# 524656_003__3.net
KiCad netlist of a schematic drawn in Altium Designer
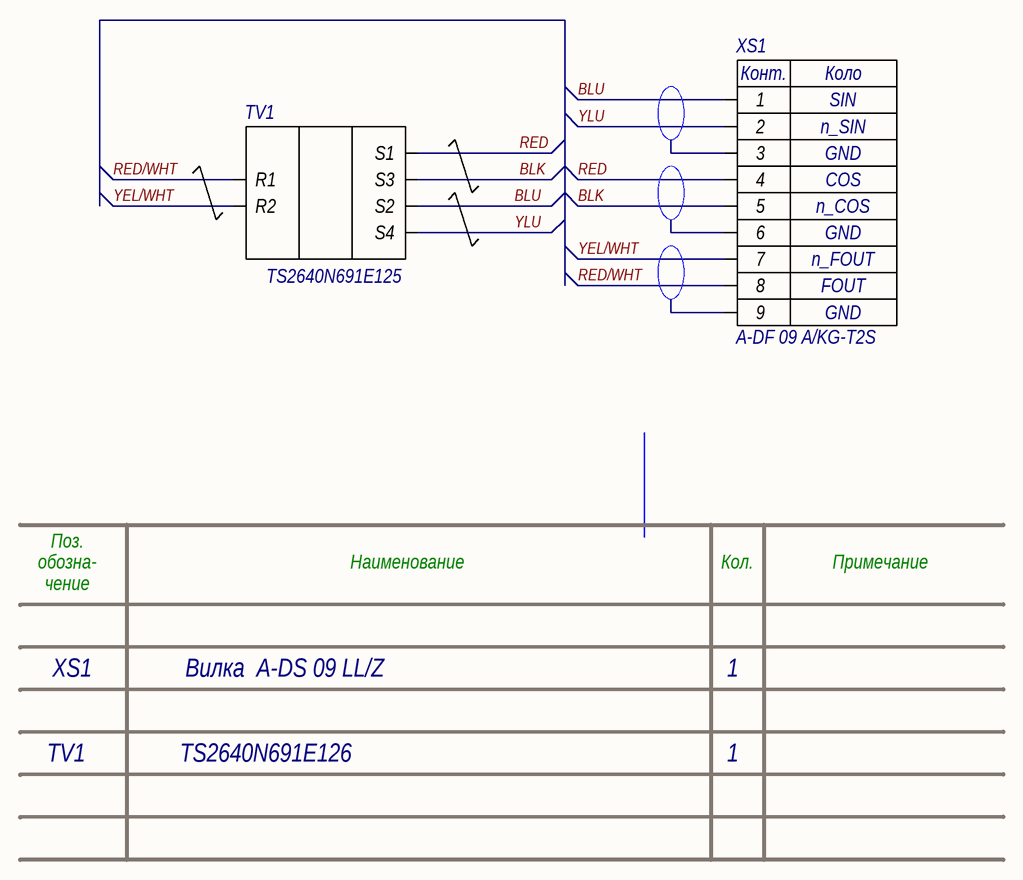
[diagram p0: АЧАД.524656.003_Э3.SchDoc]

(export (version "E")
  (design (tool "Eeschema 10.0.6"))
  (components
    (comp (ref "TV1") (value "ENGLE_SENSOR") (libsource (lib "АСК_1") (part "ENGLE_SENSOR")))
    (comp (ref "XS1") (value "A-DF 09 A/KG-T2S") (libsource (lib "АСК_1") (part "A-DF 09 A/KG-T2S")))
  )
  (nets
    (net (code "1") (name "/BLK") (class "Default")
      (node (ref "TV1") (pin "4") (pinfunction "S3_4") (pintype "passive"))
      (node (ref "XS1") (pin "5") (pinfunction "5_5") (pintype "passive"))
    )
    (net (code "2") (name "/BLU") (class "Default")
      (node (ref "TV1") (pin "5") (pinfunction "S2_5") (pintype "passive"))
      (node (ref "XS1") (pin "1") (pinfunction "1_1") (pintype "passive"))
    )
    (net (code "3") (name "/RED") (class "Default")
      (node (ref "TV1") (pin "3") (pinfunction "S1_3") (pintype "passive"))
      (node (ref "XS1") (pin "4") (pinfunction "4_4") (pintype "passive"))
    )
    (net (code "4") (name "/RED{slash}WHT") (class "Default")
      (node (ref "TV1") (pin "1") (pinfunction "R1_1") (pintype "passive"))
      (node (ref "XS1") (pin "8") (pinfunction "8_8") (pintype "passive"))
    )
    (net (code "5") (name "/YEL{slash}WHT") (class "Default")
      (node (ref "TV1") (pin "2") (pinfunction "R2_2") (pintype "passive"))
      (node (ref "XS1") (pin "7") (pinfunction "7_7") (pintype "passive"))
    )
    (net (code "6") (name "/YLU") (class "Default")
      (node (ref "TV1") (pin "6") (pinfunction "S4_6") (pintype "passive"))
      (node (ref "XS1") (pin "2") (pinfunction "2_2") (pintype "passive"))
    )
    (net (code "7") (name "unconnected-(XS1-Pad3)") (class "Default")
      (node (ref "XS1") (pin "3") (pinfunction "3_3") (pintype "passive"))
    )
    (net (code "8") (name "unconnected-(XS1-Pad6)") (class "Default")
      (node (ref "XS1") (pin "6") (pinfunction "6_6") (pintype "passive"))
    )
    (net (code "9") (name "unconnected-(XS1-Pad9)") (class "Default")
      (node (ref "XS1") (pin "9") (pinfunction "9_9") (pintype "passive"))
    )
  )
)
